# Power.net
KiCad netlist of a schematic drawn in Altium Designer
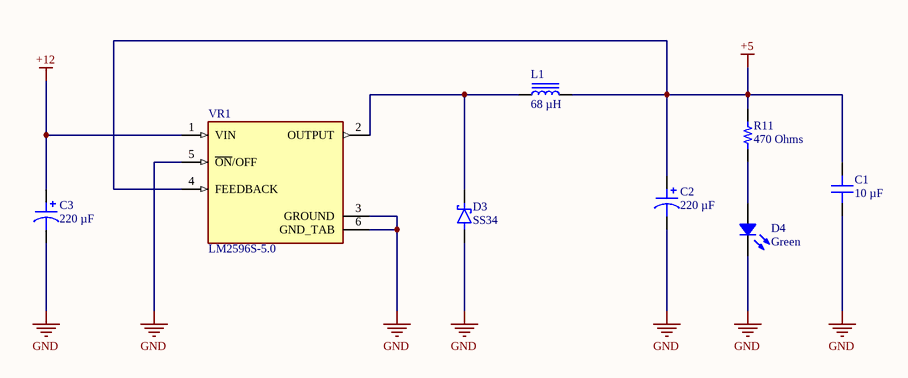
[diagram p0: Power.SchDoc]

(export (version "E")
  (design (tool "Eeschema 10.0.6"))
  (components
    (comp (ref "C1")
      (value "10 µF")
      (footprint "CAP 0603_1608")
      (description "CAP CER 10UF 25V X5R 0603")
      (fields (field (name "PART NUMBER") "TMK107BBJ106MA-T") (field (name "MANUFACTURER") "Taiyo Yuden"))
      (libsource (lib "Celestial Altium Library - altium_library") (part "Capacitor"))
    )
    (comp (ref "C2")
      (value "220 µF")
      (footprint "CAP ALSMD 8.3MM H10.5MM")
      (description "CAP ALUM 220UF 20% 25V SMD")
      (fields (field (name "PART NUMBER") "VZH221M1ETR-0810S") (field (name "MANUFACTURER") "SURGE"))
      (libsource (lib "Celestial Altium Library - altium_library") (part "Polarised Capacitor"))
    )
    (comp (ref "C3")
      (value "220 µF")
      (footprint "CAP ALSMD 8.3MM H10.5MM")
      (description "CAP ALUM 220UF 20% 25V SMD")
      (fields (field (name "PART NUMBER") "VZH221M1ETR-0810S") (field (name "MANUFACTURER") "SURGE"))
      (libsource (lib "Celestial Altium Library - altium_library") (part "Polarised Capacitor"))
    )
    (comp (ref "D3")
      (value "SS34")
      (footprint "DIOM7959X265N")
      (description "Diode Schottky 40 V 3A Surface Mount SMC (DO-214AB)")
      (fields (field (name "MF") "onsemi"))
      (libsource (lib "SS34") (part "SS34"))
    )
    (comp (ref "D4")
      (value "Green")
      (footprint "LED 0402_1005 GREEN")
      (description "LED GREEN CLEAR 0402 SMD")
      (fields (field (name "PART NUMBER") "XZVGR68W-3") (field (name "MANUFACTURER") "SunLED"))
      (libsource (lib "Celestial Altium Library - altium_library") (part "LED"))
    )
    (comp (ref "L1")
      (value "68 µH")
      (footprint "WURTH WE-PD 1210")
      (description "FIXED IND 68UH 3.2A 89 MOHM SMD")
      (fields (field (name "PART NUMBER") "7447709680") (field (name "MANUFACTURER") "Würth Elektronik"))
      (libsource (lib "Celestial Altium Library - altium_library") (part "Inductor"))
    )
    (comp (ref "R11")
      (value "470 Ohms")
      (footprint "RES 0603_1608")
      (description "RES 470 OHM 0.1% 1/10W 0603")
      (fields
        (field (name "PART NUMBER") "RN73R1JTTD4700B25")
        (field (name "MANUFACTURER") "KOA Speer Electronics, Inc.")
      )
      (libsource (lib "Celestial Altium Library - altium_library") (part "Resistor"))
    )
    (comp (ref "VR1")
      (value "LM2596S-5.0")
      (footprint "TO170P1524X483-6N")
      (description "SIMPLE SWITCHER&reg; 4.5V to 40V, 3A Low Component Count Step-Down Regulator")
      (fields (field (name "MP") "LM2596S-5.0/NOPB") (field (name "MF") "Texas Instruments"))
      (libsource (lib "LM2596S-5.0") (part "LM2596S-5.0"))
    )
  )
  (nets
    (net (code "1") (name "+5") (class "Default")
      (node (ref "C1") (pin "2") (pinfunction "2_2") (pintype "passive"))
      (node (ref "C2") (pin "1") (pinfunction "1_1") (pintype "passive"))
      (node (ref "L1") (pin "2") (pinfunction "2_2") (pintype "passive"))
      (node (ref "R11") (pin "2") (pinfunction "2_2") (pintype "passive"))
      (node (ref "VR1") (pin "4") (pinfunction "FEEDBACK_4") (pintype "input"))
    )
    (net (code "2") (name "+12") (class "Default")
      (node (ref "C3") (pin "1") (pinfunction "1_1") (pintype "passive"))
      (node (ref "VR1") (pin "1") (pinfunction "VIN_1") (pintype "input"))
    )
    (net (code "3") (name "GND") (class "Default")
      (node (ref "C1") (pin "1") (pinfunction "1_1") (pintype "passive"))
      (node (ref "C2") (pin "2") (pinfunction "2_2") (pintype "passive"))
      (node (ref "C3") (pin "2") (pinfunction "2_2") (pintype "passive"))
      (node (ref "D3") (pin "A") (pinfunction "A_A") (pintype "passive"))
      (node (ref "D4") (pin "2") (pinfunction "2_2") (pintype "passive"))
      (node (ref "VR1") (pin "3") (pinfunction "GROUND_3") (pintype "power_in"))
      (node (ref "VR1") (pin "5") (pinfunction "~{ON}/OFF_5") (pintype "input"))
      (node (ref "VR1") (pin "6") (pinfunction "GND_TAB_6") (pintype "power_in"))
    )
    (net (code "4") (name "Net-(D3-K)") (class "Default")
      (node (ref "D3") (pin "C") (pinfunction "K_C") (pintype "passive"))
      (node (ref "L1") (pin "1") (pinfunction "1_1") (pintype "passive"))
      (node (ref "VR1") (pin "2") (pinfunction "OUTPUT_2") (pintype "output"))
    )
    (net (code "5") (name "Net-(D4-Pad1)") (class "Default")
      (node (ref "D4") (pin "1") (pinfunction "1_1") (pintype "passive"))
      (node (ref "R11") (pin "1") (pinfunction "1_1") (pintype "passive"))
    )
  )
)
